# misc.net
KiCad netlist of a schematic drawn in Altium Designer
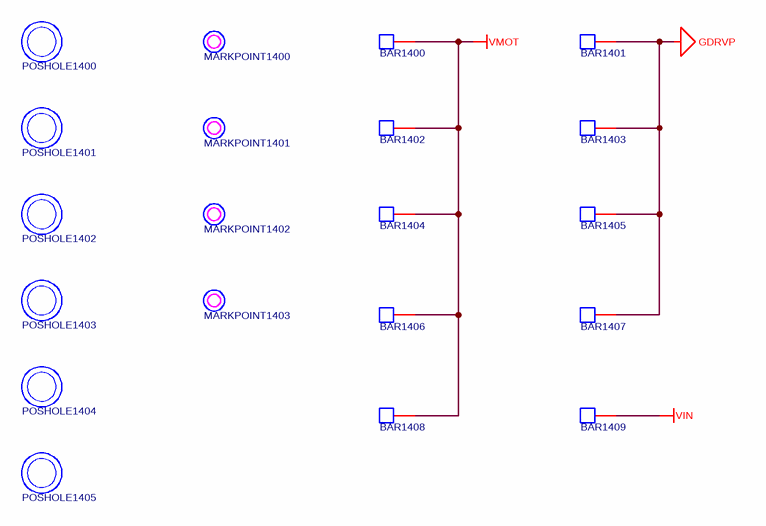
[diagram p0: misc.schdoc]

(export (version "E")
  (design (tool "Eeschema 10.0.6"))
  (components
    (comp (ref "BAR1400")
      (value "BAR")
      (footprint "mw:BAR3X20T1")
      (description "SMD copper bar for current reinforcement")
      (libsource (lib "mw") (part "BAR"))
    )
    (comp (ref "BAR1401")
      (value "BAR")
      (footprint "mw:BAR3X18T1")
      (description "SMD copper bar for current reinforcement")
      (libsource (lib "mw") (part "BAR"))
    )
    (comp (ref "BAR1402")
      (value "BAR")
      (footprint "mw:BAR3X8T1")
      (description "SMD copper bar for current reinforcement")
      (libsource (lib "mw") (part "BAR"))
    )
    (comp (ref "BAR1403")
      (value "BAR")
      (footprint "mw:BAR3X10T1")
      (description "SMD copper bar for current reinforcement")
      (libsource (lib "mw") (part "BAR"))
    )
    (comp (ref "BAR1404")
      (value "BAR")
      (footprint "mw:BAR3X8T1")
      (description "SMD copper bar for current reinforcement")
      (libsource (lib "mw") (part "BAR"))
    )
    (comp (ref "BAR1405")
      (value "BAR")
      (footprint "mw:BAR3X10T1")
      (description "SMD copper bar for current reinforcement")
      (libsource (lib "mw") (part "BAR"))
    )
    (comp (ref "BAR1406")
      (value "BAR")
      (footprint "mw:BAR3X6T1")
      (description "SMD copper bar for current reinforcement")
      (libsource (lib "mw") (part "BAR"))
    )
    (comp (ref "BAR1407")
      (value "BAR")
      (footprint "mw:BAR3X20T1")
      (description "SMD copper bar for current reinforcement")
      (libsource (lib "mw") (part "BAR"))
    )
    (comp (ref "BAR1408")
      (value "BAR")
      (footprint "mw:BAR3X18T1")
      (description "SMD copper bar for current reinforcement")
      (libsource (lib "mw") (part "BAR"))
    )
    (comp (ref "BAR1409")
      (value "BAR")
      (footprint "mw:BAR3X10T1")
      (description "SMD copper bar for current reinforcement")
      (libsource (lib "mw") (part "BAR"))
    )
    (comp (ref "MARKPOINT1400")
      (value "MARKPOINT")
      (footprint "mw:MARKPOINT-1.0")
      (libsource (lib "mw") (part "MARKPOINT"))
    )
    (comp (ref "MARKPOINT1401")
      (value "MARKPOINT")
      (footprint "mw:MARKPOINT-1.0")
      (libsource (lib "mw") (part "MARKPOINT"))
    )
    (comp (ref "MARKPOINT1402")
      (value "MARKPOINT")
      (footprint "mw:MARKPOINT-1.0")
      (libsource (lib "mw") (part "MARKPOINT"))
    )
    (comp (ref "MARKPOINT1403")
      (value "MARKPOINT")
      (footprint "mw:MARKPOINT-1.0")
      (libsource (lib "mw") (part "MARKPOINT"))
    )
    (comp (ref "POSHOLE1400")
      (value "POSHOLE")
      (footprint "mw:POSHOLE-3.2")
      (libsource (lib "mw") (part "POSHOLE"))
    )
    (comp (ref "POSHOLE1401")
      (value "POSHOLE")
      (footprint "mw:POSHOLE-3.2")
      (libsource (lib "mw") (part "POSHOLE"))
    )
    (comp (ref "POSHOLE1402")
      (value "POSHOLE")
      (footprint "mw:POSHOLE-3.2")
      (libsource (lib "mw") (part "POSHOLE"))
    )
    (comp (ref "POSHOLE1403")
      (value "POSHOLE")
      (footprint "mw:POSHOLE-3.2")
      (libsource (lib "mw") (part "POSHOLE"))
    )
    (comp (ref "POSHOLE1404")
      (value "POSHOLE")
      (footprint "mw:POSHOLE-3.2")
      (libsource (lib "mw") (part "POSHOLE"))
    )
    (comp (ref "POSHOLE1405")
      (value "POSHOLE")
      (footprint "mw:POSHOLE-3.2")
      (libsource (lib "mw") (part "POSHOLE"))
    )
  )
  (nets
    (net (code "1") (name "GDRVP") (class "Default")
      (node (ref "BAR1401") (pin "1") (pintype "passive"))
      (node (ref "BAR1403") (pin "1") (pintype "passive"))
      (node (ref "BAR1405") (pin "1") (pintype "passive"))
      (node (ref "BAR1407") (pin "1") (pintype "passive"))
    )
    (net (code "2") (name "VIN") (class "Default") (node (ref "BAR1409") (pin "1") (pintype "passive")))
    (net (code "3") (name "VMOT") (class "Default")
      (node (ref "BAR1400") (pin "1") (pintype "passive"))
      (node (ref "BAR1402") (pin "1") (pintype "passive"))
      (node (ref "BAR1404") (pin "1") (pintype "passive"))
      (node (ref "BAR1406") (pin "1") (pintype "passive"))
      (node (ref "BAR1408") (pin "1") (pintype "passive"))
    )
  )
)
